# new_esplay.net
KiCad netlist of a schematic drawn in EAGLE
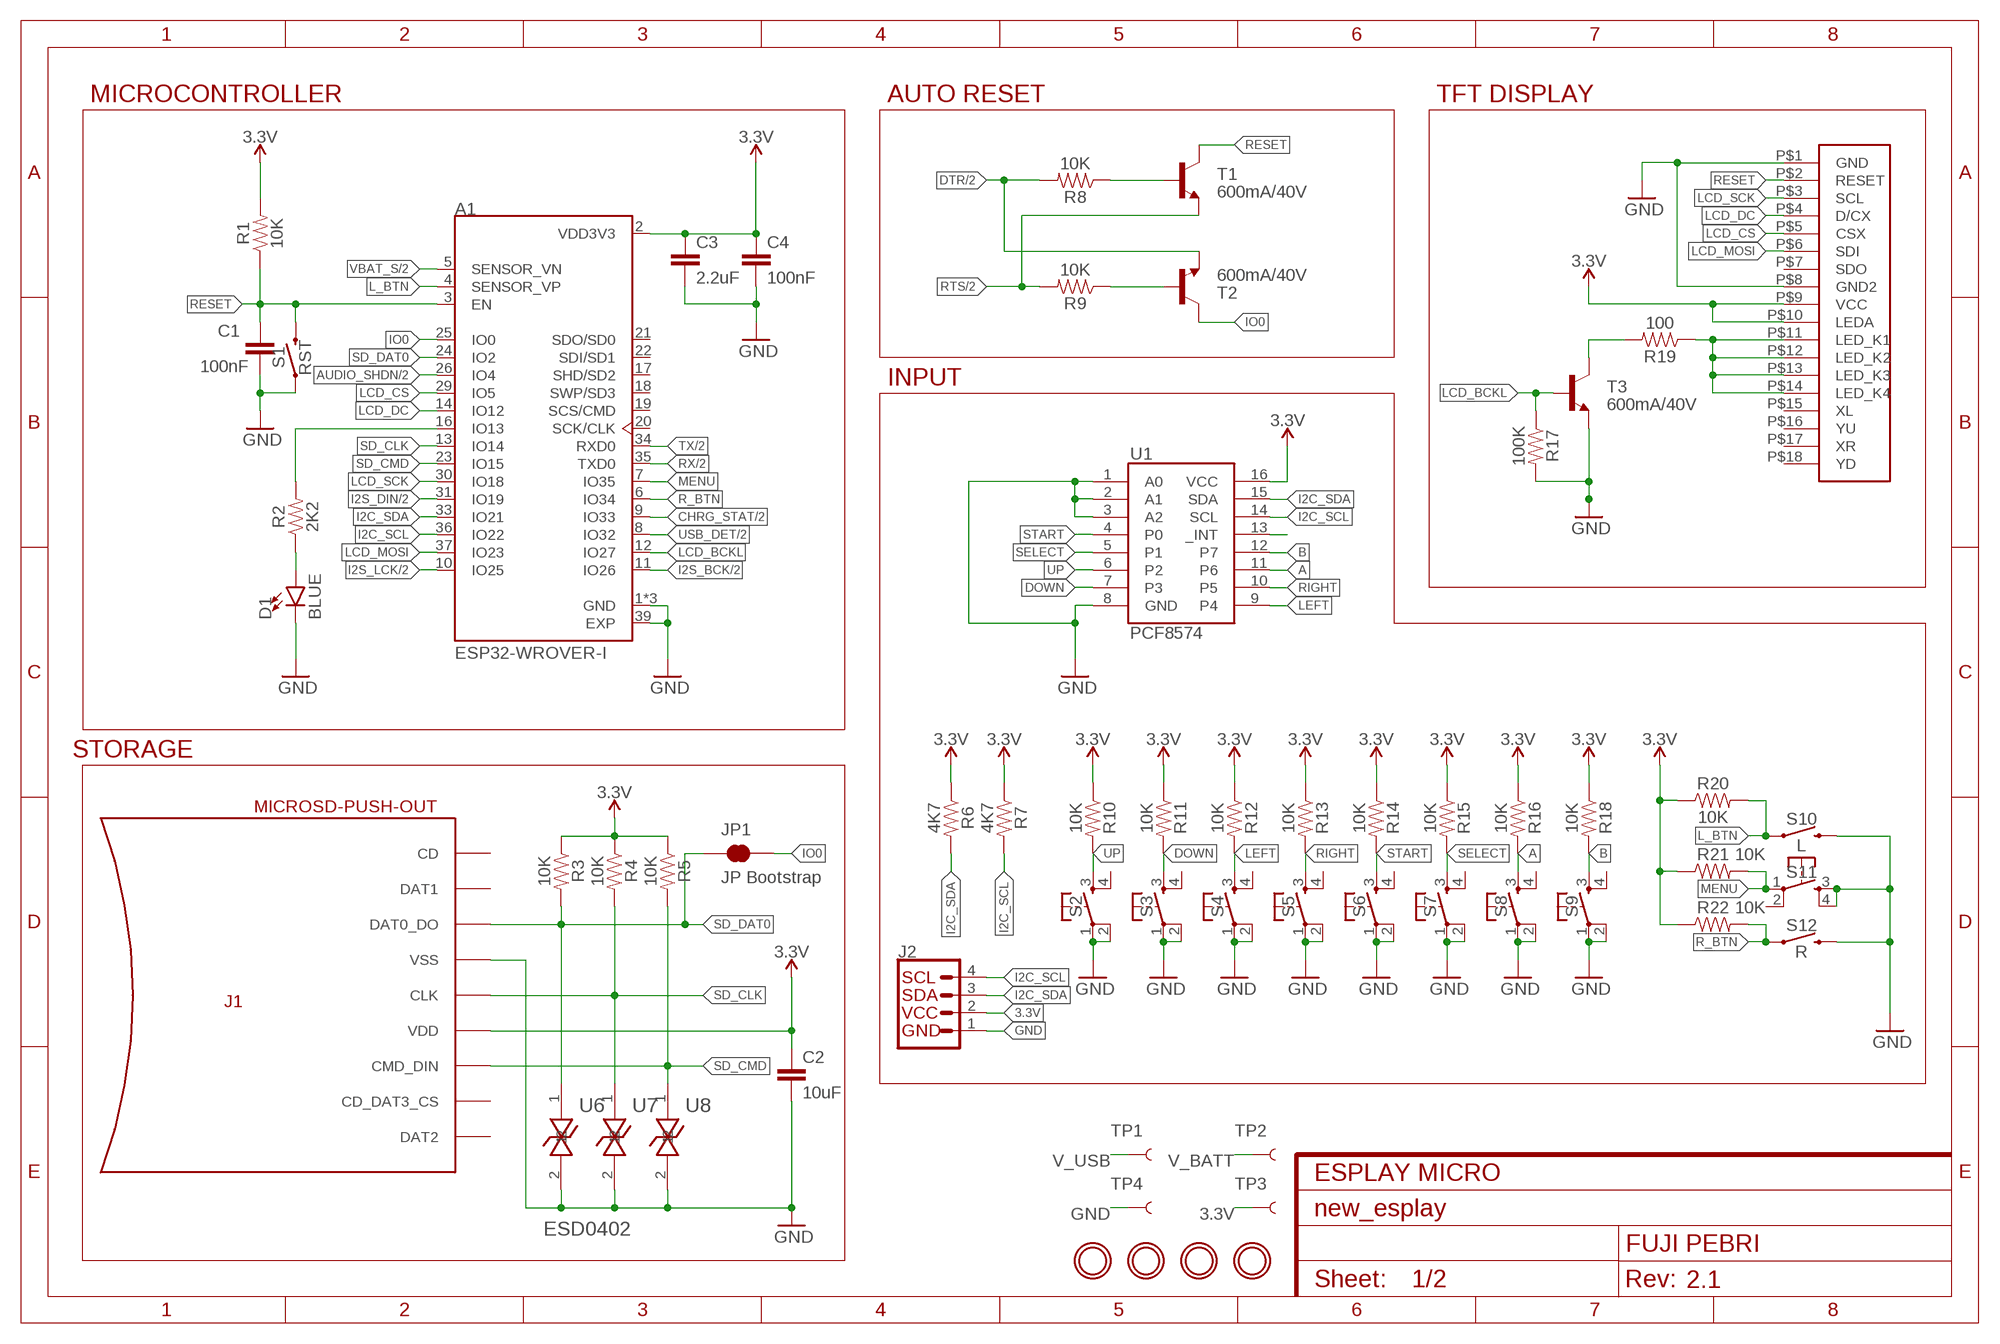
[diagram p0: schematic, sheet 1]
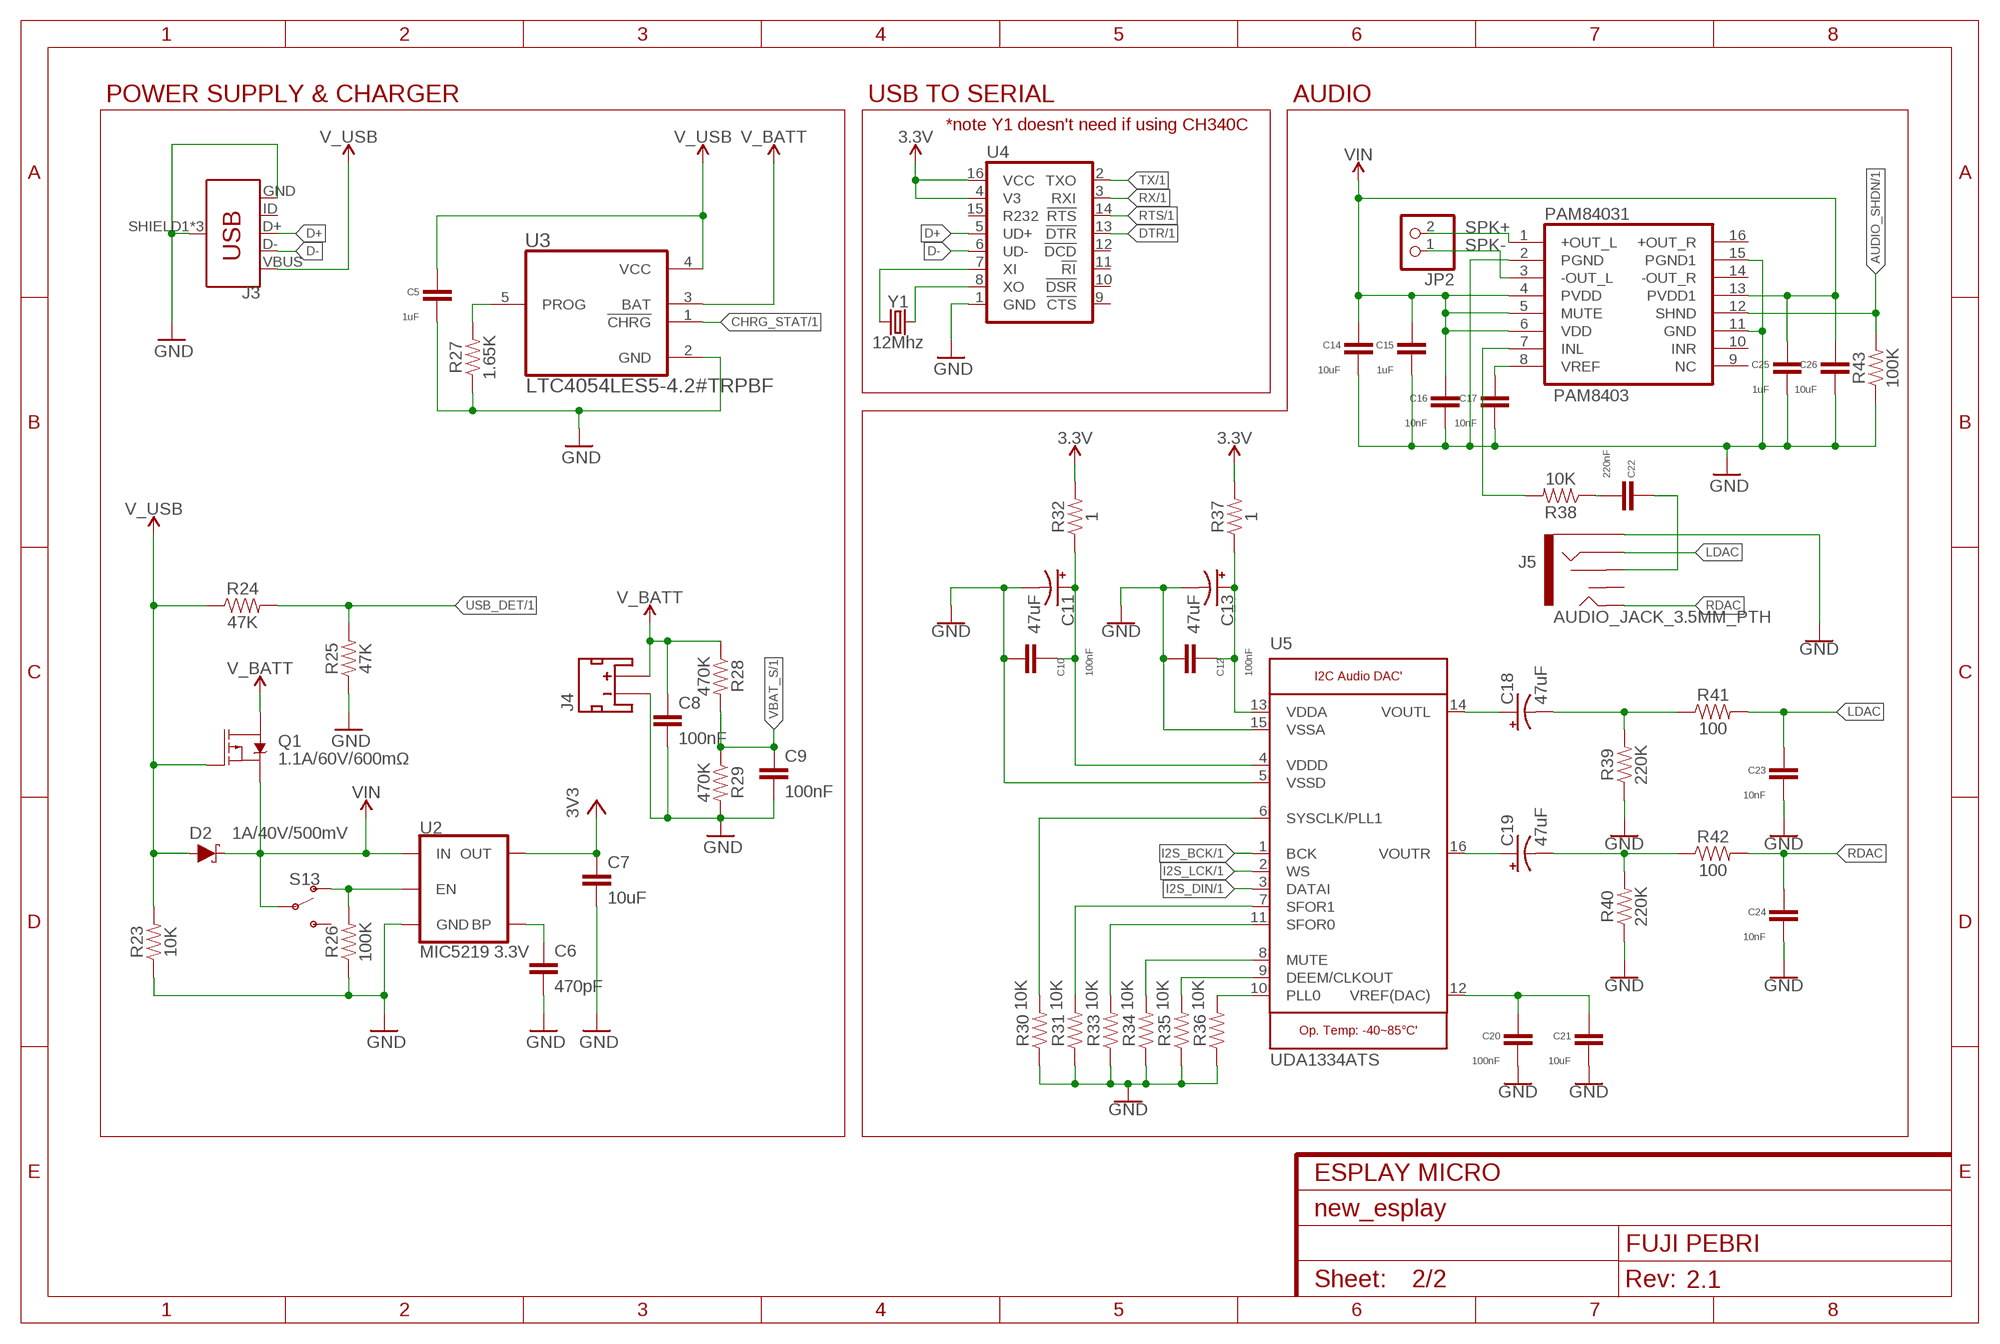
[diagram p1: schematic, sheet 2]

(export (version "E")
  (design (tool "Eeschema 10.0.6"))
  (components
    (comp (ref "A1")
      (value "ESP32-WROVER-I")
      (footprint "eagle-import:XCVR_ESP32-WROVER-I")
      (fields (field (name "MF") "Espressif Systems"))
      (libsource (lib "eagle-import") (part "ESP32-WROVER-I"))
    )
    (comp (ref "C1")
      (value "100nF")
      (footprint "eagle-import:0805")
      (libsource (lib "eagle-import") (part "2.2UF-0805-25V-(+80/-20%)"))
    )
    (comp (ref "C2")
      (value "10uF")
      (footprint "eagle-import:0805")
      (libsource (lib "eagle-import") (part "2.2UF-0805-25V-(+80/-20%)"))
    )
    (comp (ref "C3")
      (value "2.2uF")
      (footprint "eagle-import:0805")
      (libsource (lib "eagle-import") (part "2.2UF-0805-25V-(+80/-20%)"))
    )
    (comp (ref "C4")
      (value "100nF")
      (footprint "eagle-import:0805")
      (libsource (lib "eagle-import") (part "2.2UF-0805-25V-(+80/-20%)"))
    )
    (comp (ref "D1")
      (value "BLUE")
      (footprint "eagle-import:LED-0603")
      (libsource (lib "eagle-import") (part "LED-BLUE0603"))
    )
    (comp (ref "H1")
      (value "MICROBUILDER_MOUNTINGHOLE3.0THIN")
      (footprint "eagle-import:MICROBUILDER_MOUNTINGHOLE_3.0_PLATEDTHIN")
      (libsource (lib "eagle-import") (part "MICROBUILDER_MOUNTINGHOLE3.0THIN"))
    )
    (comp (ref "H2")
      (value "MICROBUILDER_MOUNTINGHOLE3.0THIN")
      (footprint "eagle-import:MICROBUILDER_MOUNTINGHOLE_3.0_PLATEDTHIN")
      (libsource (lib "eagle-import") (part "MICROBUILDER_MOUNTINGHOLE3.0THIN"))
    )
    (comp (ref "H3")
      (value "MICROBUILDER_MOUNTINGHOLE3.0THIN")
      (footprint "eagle-import:MICROBUILDER_MOUNTINGHOLE_3.0_PLATEDTHIN")
      (libsource (lib "eagle-import") (part "MICROBUILDER_MOUNTINGHOLE3.0THIN"))
    )
    (comp (ref "H4")
      (value "MICROBUILDER_MOUNTINGHOLE3.0THIN")
      (footprint "eagle-import:MICROBUILDER_MOUNTINGHOLE_3.0_PLATEDTHIN")
      (libsource (lib "eagle-import") (part "MICROBUILDER_MOUNTINGHOLE3.0THIN"))
    )
    (comp (ref "J1")
      (value "MICROSD-PUSH-OUT")
      (footprint "eagle-import:MICROSD-PUSH-OUT")
      (libsource (lib "eagle-import") (part "MICROSD-PUSH-OUT"))
    )
    (comp (ref "J2")
      (value "QWIIC_CONNECTORJS-1MM")
      (footprint "eagle-import:1X04_1MM_RA")
      (libsource (lib "eagle-import") (part "QWIIC_CONNECTORJS-1MM"))
    )
    (comp (ref "JP1")
      (value "JP Bootstrap")
      (footprint "eagle-import:SMT-JUMPER_2_NC_TRACE_NO-SILK")
      (libsource (lib "eagle-import") (part "JUMPER-SMT_2_NC_TRACE_NO-SILK"))
    )
    (comp (ref "LCD1")
      (value "ILI9341-2.4")
      (footprint "eagle-import:ILI9341-2.4")
      (libsource (lib "eagle-import") (part "ILI9341-2.4"))
    )
    (comp (ref "R1")
      (value "10K")
      (footprint "eagle-import:0805")
      (libsource (lib "eagle-import") (part "0.22OHM-0805-1/4W-1%"))
    )
    (comp (ref "R2")
      (value "2K2")
      (footprint "eagle-import:0805")
      (libsource (lib "eagle-import") (part "0.22OHM-0805-1/4W-1%"))
    )
    (comp (ref "R3")
      (value "10K")
      (footprint "eagle-import:0805")
      (libsource (lib "eagle-import") (part "0.22OHM-0805-1/4W-1%"))
    )
    (comp (ref "R4")
      (value "10K")
      (footprint "eagle-import:0805")
      (libsource (lib "eagle-import") (part "0.22OHM-0805-1/4W-1%"))
    )
    (comp (ref "R5")
      (value "10K")
      (footprint "eagle-import:0805")
      (libsource (lib "eagle-import") (part "0.22OHM-0805-1/4W-1%"))
    )
    (comp (ref "R6")
      (value "4K7")
      (footprint "eagle-import:0805")
      (libsource (lib "eagle-import") (part "0.22OHM-0805-1/4W-1%"))
    )
    (comp (ref "R7")
      (value "4K7")
      (footprint "eagle-import:0805")
      (libsource (lib "eagle-import") (part "0.22OHM-0805-1/4W-1%"))
    )
    (comp (ref "R8")
      (value "10K")
      (footprint "eagle-import:0805")
      (libsource (lib "eagle-import") (part "0.22OHM-0805-1/4W-1%"))
    )
    (comp (ref "R9")
      (value "10K")
      (footprint "eagle-import:0805")
      (libsource (lib "eagle-import") (part "0.22OHM-0805-1/4W-1%"))
    )
    (comp (ref "R10")
      (value "10K")
      (footprint "eagle-import:0805")
      (libsource (lib "eagle-import") (part "0.22OHM-0805-1/4W-1%"))
    )
    (comp (ref "R11")
      (value "10K")
      (footprint "eagle-import:0805")
      (libsource (lib "eagle-import") (part "0.22OHM-0805-1/4W-1%"))
    )
    (comp (ref "R12")
      (value "10K")
      (footprint "eagle-import:0805")
      (libsource (lib "eagle-import") (part "0.22OHM-0805-1/4W-1%"))
    )
    (comp (ref "R13")
      (value "10K")
      (footprint "eagle-import:0805")
      (libsource (lib "eagle-import") (part "0.22OHM-0805-1/4W-1%"))
    )
    (comp (ref "R14")
      (value "10K")
      (footprint "eagle-import:0805")
      (libsource (lib "eagle-import") (part "0.22OHM-0805-1/4W-1%"))
    )
    (comp (ref "R15")
      (value "10K")
      (footprint "eagle-import:0805")
      (libsource (lib "eagle-import") (part "0.22OHM-0805-1/4W-1%"))
    )
    (comp (ref "R16")
      (value "10K")
      (footprint "eagle-import:0805")
      (libsource (lib "eagle-import") (part "0.22OHM-0805-1/4W-1%"))
    )
    (comp (ref "R17")
      (value "100K")
      (footprint "eagle-import:0805")
      (libsource (lib "eagle-import") (part "0.22OHM-0805-1/4W-1%"))
    )
    (comp (ref "R18")
      (value "10K")
      (footprint "eagle-import:0805")
      (libsource (lib "eagle-import") (part "0.22OHM-0805-1/4W-1%"))
    )
    (comp (ref "R19")
      (value "100")
      (footprint "eagle-import:0805")
      (libsource (lib "eagle-import") (part "0.22OHM-0805-1/4W-1%"))
    )
    (comp (ref "R20")
      (value "10K")
      (footprint "eagle-import:0805")
      (libsource (lib "eagle-import") (part "0.22OHM-0805-1/4W-1%"))
    )
    (comp (ref "R21")
      (value "10K")
      (footprint "eagle-import:0805")
      (libsource (lib "eagle-import") (part "0.22OHM-0805-1/4W-1%"))
    )
    (comp (ref "R22")
      (value "10K")
      (footprint "eagle-import:0805")
      (libsource (lib "eagle-import") (part "0.22OHM-0805-1/4W-1%"))
    )
    (comp (ref "S1")
      (value "RST")
      (footprint "eagle-import:TACTILE_SWITCH_SMD_4.6X2.8MM")
      (libsource (lib "eagle-import") (part "MOMENTARY-SWITCH-SPST-SMD-4.6X2.8MM"))
    )
    (comp (ref "S2")
      (value "MOMENTARY-SWITCH-SPST-2-SMD-5.2MM")
      (footprint "eagle-import:TACTILE_SWITCH_SMD_5.2MM")
      (libsource (lib "eagle-import") (part "MOMENTARY-SWITCH-SPST-2-SMD-5.2MM"))
    )
    (comp (ref "S3")
      (value "MOMENTARY-SWITCH-SPST-2-SMD-5.2MM")
      (footprint "eagle-import:TACTILE_SWITCH_SMD_5.2MM")
      (libsource (lib "eagle-import") (part "MOMENTARY-SWITCH-SPST-2-SMD-5.2MM"))
    )
    (comp (ref "S4")
      (value "MOMENTARY-SWITCH-SPST-2-SMD-5.2MM")
      (footprint "eagle-import:TACTILE_SWITCH_SMD_5.2MM")
      (libsource (lib "eagle-import") (part "MOMENTARY-SWITCH-SPST-2-SMD-5.2MM"))
    )
    (comp (ref "S5")
      (value "MOMENTARY-SWITCH-SPST-2-SMD-5.2MM")
      (footprint "eagle-import:TACTILE_SWITCH_SMD_5.2MM")
      (libsource (lib "eagle-import") (part "MOMENTARY-SWITCH-SPST-2-SMD-5.2MM"))
    )
    (comp (ref "S6")
      (value "MOMENTARY-SWITCH-SPST-2-SMD-5.2MM")
      (footprint "eagle-import:TACTILE_SWITCH_SMD_5.2MM")
      (libsource (lib "eagle-import") (part "MOMENTARY-SWITCH-SPST-2-SMD-5.2MM"))
    )
    (comp (ref "S7")
      (value "MOMENTARY-SWITCH-SPST-2-SMD-5.2MM")
      (footprint "eagle-import:TACTILE_SWITCH_SMD_5.2MM")
      (libsource (lib "eagle-import") (part "MOMENTARY-SWITCH-SPST-2-SMD-5.2MM"))
    )
    (comp (ref "S8")
      (value "MOMENTARY-SWITCH-SPST-2-SMD-5.2MM")
      (footprint "eagle-import:TACTILE_SWITCH_SMD_5.2MM")
      (libsource (lib "eagle-import") (part "MOMENTARY-SWITCH-SPST-2-SMD-5.2MM"))
    )
    (comp (ref "S9")
      (value "MOMENTARY-SWITCH-SPST-2-SMD-5.2MM")
      (footprint "eagle-import:TACTILE_SWITCH_SMD_5.2MM")
      (libsource (lib "eagle-import") (part "MOMENTARY-SWITCH-SPST-2-SMD-5.2MM"))
    )
    (comp (ref "S10")
      (value "L")
      (footprint "eagle-import:TACTILE_SWITCH_PTH_RIGHT_ANGLE_KIT")
      (libsource (lib "eagle-import") (part "MOMENTARY-SWITCH-SPST-PTH-RIGHT-ANGLE-KIT"))
    )
    (comp (ref "S11")
      (value "MOMENTARY-SWITCH-SPST-2-SMD-5.2MM")
      (footprint "eagle-import:TACTILE_SWITCH_SMD_5.2MM")
      (libsource (lib "eagle-import") (part "MOMENTARY-SWITCH-SPST-2-SMD-5.2MM"))
    )
    (comp (ref "S12")
      (value "R")
      (footprint "eagle-import:TACTILE_SWITCH_PTH_RIGHT_ANGLE_KIT")
      (libsource (lib "eagle-import") (part "MOMENTARY-SWITCH-SPST-PTH-RIGHT-ANGLE-KIT"))
    )
    (comp (ref "T1")
      (value "600mA/40V")
      (footprint "eagle-import:SOT23-3")
      (libsource (lib "eagle-import") (part "TRANS_NPN-MMBT2222AL"))
    )
    (comp (ref "T2")
      (value "600mA/40V")
      (footprint "eagle-import:SOT23-3")
      (libsource (lib "eagle-import") (part "TRANS_NPN-MMBT2222AL"))
    )
    (comp (ref "T3")
      (value "600mA/40V")
      (footprint "eagle-import:SOT23-3")
      (libsource (lib "eagle-import") (part "TRANS_NPN-MMBT2222AL"))
    )
    (comp (ref "TP1")
      (value "TEST-POINT3")
      (footprint "eagle-import:PAD.03X.03")
      (libsource (lib "eagle-import") (part "TEST-POINT3"))
    )
    (comp (ref "TP2")
      (value "TEST-POINT3")
      (footprint "eagle-import:PAD.03X.03")
      (libsource (lib "eagle-import") (part "TEST-POINT3"))
    )
    (comp (ref "TP3")
      (value "TEST-POINT3")
      (footprint "eagle-import:PAD.03X.03")
      (libsource (lib "eagle-import") (part "TEST-POINT3"))
    )
    (comp (ref "TP4")
      (value "TEST-POINT3")
      (footprint "eagle-import:PAD.03X.03")
      (libsource (lib "eagle-import") (part "TEST-POINT3"))
    )
    (comp (ref "U1")
      (value "PCF8574")
      (footprint "eagle-import:SO16")
      (fields (field (name "MF") "Texas Instruments"))
      (libsource (lib "eagle-import") (part "PCF8574"))
    )
    (comp (ref "U6")
      (value "ESD0402")
      (footprint "eagle-import:ESD0402")
      (libsource (lib "eagle-import") (part "ESD0402"))
    )
    (comp (ref "U7")
      (value "ESD0402")
      (footprint "eagle-import:ESD0402")
      (libsource (lib "eagle-import") (part "ESD0402"))
    )
    (comp (ref "U8")
      (value "ESD0402")
      (footprint "eagle-import:ESD0402")
      (libsource (lib "eagle-import") (part "ESD0402"))
    )
    (comp (ref "C5")
      (value "1uF")
      (footprint "eagle-import:0805")
      (libsource (lib "eagle-import") (part "2.2UF-0805-25V-(+80/-20%)"))
    )
    (comp (ref "C6")
      (value "470pF")
      (footprint "eagle-import:0805")
      (libsource (lib "eagle-import") (part "2.2UF-0805-25V-(+80/-20%)"))
    )
    (comp (ref "C7")
      (value "10uF")
      (footprint "eagle-import:0805")
      (libsource (lib "eagle-import") (part "2.2UF-0805-25V-(+80/-20%)"))
    )
    (comp (ref "C8")
      (value "100nF")
      (footprint "eagle-import:0805")
      (libsource (lib "eagle-import") (part "2.2UF-0805-25V-(+80/-20%)"))
    )
    (comp (ref "C9")
      (value "100nF")
      (footprint "eagle-import:0805")
      (libsource (lib "eagle-import") (part "2.2UF-0805-25V-(+80/-20%)"))
    )
    (comp (ref "C10")
      (value "100nF")
      (footprint "eagle-import:0805")
      (libsource (lib "eagle-import") (part "2.2UF-0805-25V-(+80/-20%)"))
    )
    (comp (ref "C11")
      (value "47uF")
      (footprint "eagle-import:EIA3528")
      (libsource (lib "eagle-import") (part "47UF-POLAR-EIA3528-10V-10%"))
    )
    (comp (ref "C12")
      (value "100nF")
      (footprint "eagle-import:0805")
      (libsource (lib "eagle-import") (part "2.2UF-0805-25V-(+80/-20%)"))
    )
    (comp (ref "C13")
      (value "47uF")
      (footprint "eagle-import:EIA3528")
      (libsource (lib "eagle-import") (part "47UF-POLAR-EIA3528-10V-10%"))
    )
    (comp (ref "C14")
      (value "10uF")
      (footprint "eagle-import:0805")
      (libsource (lib "eagle-import") (part "2.2UF-0805-25V-(+80/-20%)"))
    )
    (comp (ref "C15")
      (value "1uF")
      (footprint "eagle-import:0805")
      (libsource (lib "eagle-import") (part "2.2UF-0805-25V-(+80/-20%)"))
    )
    (comp (ref "C16")
      (value "10nF")
      (footprint "eagle-import:0805")
      (libsource (lib "eagle-import") (part "2.2UF-0805-25V-(+80/-20%)"))
    )
    (comp (ref "C17")
      (value "10nF")
      (footprint "eagle-import:0805")
      (libsource (lib "eagle-import") (part "2.2UF-0805-25V-(+80/-20%)"))
    )
    (comp (ref "C18")
      (value "47uF")
      (footprint "eagle-import:EIA3528")
      (libsource (lib "eagle-import") (part "47UF-POLAR-EIA3528-10V-10%"))
    )
    (comp (ref "C19")
      (value "47uF")
      (footprint "eagle-import:EIA3528")
      (libsource (lib "eagle-import") (part "47UF-POLAR-EIA3528-10V-10%"))
    )
    (comp (ref "C20")
      (value "100nF")
      (footprint "eagle-import:0805")
      (libsource (lib "eagle-import") (part "2.2UF-0805-25V-(+80/-20%)"))
    )
    (comp (ref "C21")
      (value "10uF")
      (footprint "eagle-import:0805")
      (libsource (lib "eagle-import") (part "2.2UF-0805-25V-(+80/-20%)"))
    )
    (comp (ref "C22")
      (value "220nF")
      (footprint "eagle-import:0805")
      (libsource (lib "eagle-import") (part "2.2UF-0805-25V-(+80/-20%)"))
    )
    (comp (ref "C23")
      (value "10nF")
      (footprint "eagle-import:0805")
      (libsource (lib "eagle-import") (part "2.2UF-0805-25V-(+80/-20%)"))
    )
    (comp (ref "C24")
      (value "10nF")
      (footprint "eagle-import:0805")
      (libsource (lib "eagle-import") (part "2.2UF-0805-25V-(+80/-20%)"))
    )
    (comp (ref "C25")
      (value "1uF")
      (footprint "eagle-import:0805")
      (libsource (lib "eagle-import") (part "2.2UF-0805-25V-(+80/-20%)"))
    )
    (comp (ref "C26")
      (value "10uF")
      (footprint "eagle-import:0805")
      (libsource (lib "eagle-import") (part "2.2UF-0805-25V-(+80/-20%)"))
    )
    (comp (ref "D2")
      (value "1A/40V/500mV")
      (footprint "eagle-import:SMA-DIODE")
      (libsource (lib "eagle-import") (part "DIODE-SCHOTTKY-SS14"))
    )
    (comp (ref "J3")
      (value "USB_MICRO-B_FEMALE-SMT")
      (footprint "eagle-import:USB-B-MICRO-SMD")
      (libsource (lib "eagle-import") (part "USB_MICRO-B_FEMALE-SMT"))
    )
    (comp (ref "J4")
      (value "JST_2MM_MALE")
      (footprint "eagle-import:JST-2-SMD")
      (libsource (lib "eagle-import") (part "JST_2MM_MALE"))
    )
    (comp (ref "J5")
      (value "AUDIO_JACK_3.5MM_PTH")
      (footprint "eagle-import:AUDIO-JACK")
      (libsource (lib "eagle-import") (part "AUDIO_JACK_3.5MM_PTH"))
    )
    (comp (ref "JP2")
      (value "PINHD-1X2_2.00")
      (footprint "eagle-import:1X02M")
      (libsource (lib "eagle-import") (part "PINHD-1X2_2.00"))
    )
    (comp (ref "PAM84031")
      (value "PAM8403")
      (footprint "eagle-import:SOP-16")
      (libsource (lib "eagle-import") (part "PAM8403"))
    )
    (comp (ref "Q1")
      (value "1.1A/60V/600mΩ")
      (footprint "eagle-import:SOT23-3")
      (libsource (lib "eagle-import") (part "MOSFET_PCH-SI2309DS"))
    )
    (comp (ref "R23")
      (value "10K")
      (footprint "eagle-import:0805")
      (libsource (lib "eagle-import") (part "0.22OHM-0805-1/4W-1%"))
    )
    (comp (ref "R24")
      (value "47K")
      (footprint "eagle-import:0805")
      (libsource (lib "eagle-import") (part "0.22OHM-0805-1/4W-1%"))
    )
    (comp (ref "R25")
      (value "47K")
      (footprint "eagle-import:0805")
      (libsource (lib "eagle-import") (part "0.22OHM-0805-1/4W-1%"))
    )
    (comp (ref "R26")
      (value "100K")
      (footprint "eagle-import:0805")
      (libsource (lib "eagle-import") (part "0.22OHM-0805-1/4W-1%"))
    )
    (comp (ref "R27")
      (value "1.65K")
      (footprint "eagle-import:0805")
      (libsource (lib "eagle-import") (part "0.3OHM-0805-1/8W-1%"))
    )
    (comp (ref "R28")
      (value "470K")
      (footprint "eagle-import:0805")
      (libsource (lib "eagle-import") (part "0.22OHM-0805-1/4W-1%"))
    )
    (comp (ref "R29")
      (value "470K")
      (footprint "eagle-import:0805")
      (libsource (lib "eagle-import") (part "0.22OHM-0805-1/4W-1%"))
    )
    (comp (ref "R30")
      (value "10K")
      (footprint "eagle-import:0805")
      (libsource (lib "eagle-import") (part "0.3OHM-0805-1/8W-1%"))
    )
    (comp (ref "R31")
      (value "10K")
      (footprint "eagle-import:0805")
      (libsource (lib "eagle-import") (part "0.3OHM-0805-1/8W-1%"))
    )
    (comp (ref "R32")
      (value "1")
      (footprint "eagle-import:0805")
      (libsource (lib "eagle-import") (part "0.3OHM-0805-1/8W-1%"))
    )
    (comp (ref "R33")
      (value "10K")
      (footprint "eagle-import:0805")
      (libsource (lib "eagle-import") (part "0.3OHM-0805-1/8W-1%"))
    )
    (comp (ref "R34")
      (value "10K")
      (footprint "eagle-import:0805")
      (libsource (lib "eagle-import") (part "0.3OHM-0805-1/8W-1%"))
    )
    (comp (ref "R35")
      (value "10K")
      (footprint "eagle-import:0805")
      (libsource (lib "eagle-import") (part "0.3OHM-0805-1/8W-1%"))
    )
    (comp (ref "R36")
      (value "10K")
      (footprint "eagle-import:0805")
      (libsource (lib "eagle-import") (part "0.3OHM-0805-1/8W-1%"))
    )
    (comp (ref "R37")
      (value "1")
      (footprint "eagle-import:0805")
      (libsource (lib "eagle-import") (part "0.3OHM-0805-1/8W-1%"))
    )
    (comp (ref "R38")
      (value "10K")
      (footprint "eagle-import:0805")
      (libsource (lib "eagle-import") (part "0.3OHM-0805-1/8W-1%"))
    )
    (comp (ref "R39")
      (value "220K")
      (footprint "eagle-import:0805")
      (libsource (lib "eagle-import") (part "0.3OHM-0805-1/8W-1%"))
    )
    (comp (ref "R40")
      (value "220K")
      (footprint "eagle-import:0805")
      (libsource (lib "eagle-import") (part "0.3OHM-0805-1/8W-1%"))
    )
    (comp (ref "R41")
      (value "100")
      (footprint "eagle-import:0805")
      (libsource (lib "eagle-import") (part "0.3OHM-0805-1/8W-1%"))
    )
    (comp (ref "R42")
      (value "100")
      (footprint "eagle-import:0805")
      (libsource (lib "eagle-import") (part "0.3OHM-0805-1/8W-1%"))
    )
    (comp (ref "R43")
      (value "100K")
      (footprint "eagle-import:0805")
      (libsource (lib "eagle-import") (part "0.3OHM-0805-1/8W-1%"))
    )
    (comp (ref "S13")
      (value "SWITCH-SPDT-SMD-RIGHT-ANGLE")
      (footprint "eagle-import:SWITCH_SPST_SMD_A")
      (libsource (lib "eagle-import") (part "SWITCH-SPDT-SMD-RIGHT-ANGLE"))
    )
    (comp (ref "U2")
      (value "MIC5219 3.3V")
      (footprint "eagle-import:SOT23-5")
      (libsource (lib "eagle-import") (part "V_REG_MIC52193.3V"))
    )
    (comp (ref "U3")
      (value "LTC4054LES5-4.2#TRPBF")
      (footprint "eagle-import:SOT95P280X100-5N")
      (fields
        (field (name "DIGI-KEY_PART_NUMBER") "LTC4054LES5-4.2#TRPBFCT-ND")
        (field (name "MF") "Linear Technology/Analog")
      )
      (libsource (lib "eagle-import") (part "LTC4054LES5-4.2#TRPBF"))
    )
    (comp (ref "U4")
      (value "CH340G")
      (footprint "eagle-import:SO016")
      (libsource (lib "eagle-import") (part "CH340GSMD"))
    )
    (comp (ref "U5")
      (value "UDA1334ATS")
      (footprint "eagle-import:MICROBUILDER_SSOP16_4.4MM")
      (libsource (lib "eagle-import") (part "MICROBUILDER_AUDIO_I2S_UDA1334{dblquote}{dblquote}"))
    )
    (comp (ref "Y1")
      (value "12Mhz")
      (footprint "eagle-import:CRYSTAL-SMD-5X3.2-4PAD")
      (libsource (lib "eagle-import") (part "CRYSTALSMD-5X3.2-4PAD"))
    )
  )
  (nets
    (net (code "1") (name "3.3V") (class "Default")
      (node (ref "A1") (pin "2") (pinfunction "VDD3V3_2") (pintype "power_in"))
      (node (ref "C2") (pin "1") (pinfunction "1_1") (pintype "passive"))
      (node (ref "C3") (pin "1") (pinfunction "1_1") (pintype "passive"))
      (node (ref "C4") (pin "1") (pinfunction "1_1") (pintype "passive"))
      (node (ref "C7") (pin "1") (pinfunction "1_1") (pintype "passive"))
      (node (ref "J1") (pin "4") (pinfunction "VDD_4") (pintype "bidirectional"))
      (node (ref "J2") (pin "2") (pinfunction "2_2") (pintype "power_in"))
      (node (ref "LCD1") (pin "P$10") (pinfunction "LEDA_P$10") (pintype "bidirectional"))
      (node (ref "LCD1") (pin "P$9") (pinfunction "VCC_P$9") (pintype "bidirectional"))
      (node (ref "R1") (pin "2") (pinfunction "2_2") (pintype "passive"))
      (node (ref "R10") (pin "1") (pinfunction "1_1") (pintype "passive"))
      (node (ref "R11") (pin "1") (pinfunction "1_1") (pintype "passive"))
      (node (ref "R12") (pin "1") (pinfunction "1_1") (pintype "passive"))
      (node (ref "R13") (pin "1") (pinfunction "1_1") (pintype "passive"))
      (node (ref "R14") (pin "1") (pinfunction "1_1") (pintype "passive"))
      (node (ref "R15") (pin "1") (pinfunction "1_1") (pintype "passive"))
      (node (ref "R16") (pin "1") (pinfunction "1_1") (pintype "passive"))
      (node (ref "R18") (pin "1") (pinfunction "1_1") (pintype "passive"))
      (node (ref "R20") (pin "1") (pinfunction "1_1") (pintype "passive"))
      (node (ref "R21") (pin "1") (pinfunction "1_1") (pintype "passive"))
      (node (ref "R22") (pin "1") (pinfunction "1_1") (pintype "passive"))
      (node (ref "R3") (pin "1") (pinfunction "1_1") (pintype "passive"))
      (node (ref "R32") (pin "2") (pinfunction "2_2") (pintype "passive"))
      (node (ref "R37") (pin "2") (pinfunction "2_2") (pintype "passive"))
      (node (ref "R4") (pin "1") (pinfunction "1_1") (pintype "passive"))
      (node (ref "R5") (pin "1") (pinfunction "1_1") (pintype "passive"))
      (node (ref "R6") (pin "1") (pinfunction "1_1") (pintype "passive"))
      (node (ref "R7") (pin "1") (pinfunction "1_1") (pintype "passive"))
      (node (ref "TP3") (pin "P$1") (pinfunction "1_P$1") (pintype "bidirectional"))
      (node (ref "U1") (pin "16") (pinfunction "VCC_16") (pintype "bidirectional"))
      (node (ref "U2") (pin "5") (pinfunction "OUT_5") (pintype "passive"))
      (node (ref "U4") (pin "16") (pinfunction "VCC_16") (pintype "bidirectional"))
      (node (ref "U4") (pin "4") (pinfunction "V3_4") (pintype "bidirectional"))
    )
    (net (code "2") (name "A") (class "Default")
      (node (ref "R16") (pin "2") (pinfunction "2_2") (pintype "passive"))
      (node (ref "S8") (pin "3") (pinfunction "3_3") (pintype "passive"))
      (node (ref "U1") (pin "11") (pinfunction "P6_11") (pintype "bidirectional"))
    )
    (net (code "3") (name "AUDIO_SHDN") (class "Default")
      (node (ref "A1") (pin "26") (pinfunction "IO4_26") (pintype "bidirectional"))
      (node (ref "PAM84031") (pin "12") (pinfunction "SHND_12") (pintype "output"))
      (node (ref "R43") (pin "2") (pinfunction "2_2") (pintype "passive"))
    )
    (net (code "4") (name "B") (class "Default")
      (node (ref "R18") (pin "2") (pinfunction "2_2") (pintype "passive"))
      (node (ref "S9") (pin "3") (pinfunction "3_3") (pintype "passive"))
      (node (ref "U1") (pin "12") (pinfunction "P7_12") (pintype "bidirectional"))
    )
    (net (code "5") (name "CHRG_STAT") (class "Default")
      (node (ref "A1") (pin "9") (pinfunction "IO33_9") (pintype "bidirectional"))
      (node (ref "U3") (pin "1") (pinfunction "~{CHRG}_1") (pintype "output"))
    )
    (net (code "6") (name "D+") (class "Default")
      (node (ref "J3") (pin "D+") (pinfunction "D+_D+") (pintype "bidirectional"))
      (node (ref "U4") (pin "5") (pinfunction "UD+_5") (pintype "bidirectional"))
    )
    (net (code "7") (name "D-") (class "Default")
      (node (ref "J3") (pin "D-") (pinfunction "D-_D-") (pintype "bidirectional"))
      (node (ref "U4") (pin "6") (pinfunction "UD-_6") (pintype "bidirectional"))
    )
    (net (code "8") (name "DOWN") (class "Default")
      (node (ref "R11") (pin "2") (pinfunction "2_2") (pintype "passive"))
      (node (ref "S3") (pin "3") (pinfunction "3_3") (pintype "passive"))
      (node (ref "U1") (pin "7") (pinfunction "P3_7") (pintype "bidirectional"))
    )
    (net (code "9") (name "DTR") (class "Default")
      (node (ref "R8") (pin "2") (pinfunction "2_2") (pintype "passive"))
      (node (ref "T2") (pin "2") (pinfunction "E_2") (pintype "passive"))
      (node (ref "U4") (pin "13") (pinfunction "~{DTR}_13") (pintype "bidirectional"))
    )
    (net (code "10") (name "GND") (class "Default")
      (node (ref "A1") (pin "1") (pinfunction "GND_1") (pintype "power_in"))
      (node (ref "A1") (pin "15") (pinfunction "GND_15") (pintype "power_in"))
      (node (ref "A1") (pin "38") (pinfunction "GND_38") (pintype "power_in"))
      (node (ref "A1") (pin "39") (pinfunction "EXP_39") (pintype "power_in"))
      (node (ref "C1") (pin "2") (pinfunction "2_2") (pintype "passive"))
      (node (ref "C10") (pin "1") (pinfunction "1_1") (pintype "passive"))
      (node (ref "C11") (pin "C") (pinfunction "-_C") (pintype "passive"))
      (node (ref "C12") (pin "1") (pinfunction "1_1") (pintype "passive"))
      (node (ref "C13") (pin "C") (pinfunction "-_C") (pintype "passive"))
      (node (ref "C14") (pin "1") (pinfunction "1_1") (pintype "passive"))
      (node (ref "C15") (pin "1") (pinfunction "1_1") (pintype "passive"))
      (node (ref "C16") (pin "1") (pinfunction "1_1") (pintype "passive"))
      (node (ref "C17") (pin "1") (pinfunction "1_1") (pintype "passive"))
      (node (ref "C2") (pin "2") (pinfunction "2_2") (pintype "passive"))
      (node (ref "C20") (pin "1") (pinfunction "1_1") (pintype "passive"))
      (node (ref "C21") (pin "1") (pinfunction "1_1") (pintype "passive"))
      (node (ref "C23") (pin "1") (pinfunction "1_1") (pintype "passive"))
      (node (ref "C24") (pin "1") (pinfunction "1_1") (pintype "passive"))
      (node (ref "C25") (pin "1") (pinfunction "1_1") (pintype "passive"))
      (node (ref "C26") (pin "1") (pinfunction "1_1") (pintype "passive"))
      (node (ref "C3") (pin "2") (pinfunction "2_2") (pintype "passive"))
      (node (ref "C4") (pin "2") (pinfunction "2_2") (pintype "passive"))
      (node (ref "C5") (pin "1") (pinfunction "1_1") (pintype "passive"))
      (node (ref "C6") (pin "2") (pinfunction "2_2") (pintype "passive"))
      (node (ref "C7") (pin "2") (pinfunction "2_2") (pintype "passive"))
      (node (ref "C8") (pin "2") (pinfunction "2_2") (pintype "passive"))
      (node (ref "C9") (pin "2") (pinfunction "2_2") (pintype "passive"))
      (node (ref "D1") (pin "C") (pinfunction "C_C") (pintype "passive"))
      (node (ref "J1") (pin "6") (pinfunction "VSS_6") (pintype "bidirectional"))
      (node (ref "J1") (pin "G1") (pinfunction "VSS_G1") (pintype "bidirectional"))
      (node (ref "J1") (pin "G2") (pinfunction "VSS_G2") (pintype "bidirectional"))
      (node (ref "J1") (pin "G3") (pinfunction "VSS_G3") (pintype "bidirectional"))
      (node (ref "J1") (pin "G4") (pinfunction "VSS_G4") (pintype "bidirectional"))
      (node (ref "J2") (pin "1") (pinfunction "1_1") (pintype "power_in"))
      (node (ref "J3") (pin "GND") (pinfunction "GND_GND") (pintype "power_in"))
      (node (ref "J3") (pin "SHIELD1") (pinfunction "SHIELD_SHIELD1") (pintype "bidirectional"))
      (node (ref "J3") (pin "SHIELD2") (pinfunction "SHIELD_SHIELD2") (pintype "bidirectional"))
      (node (ref "J3") (pin "SHIELD3") (pinfunction "SHIELD_SHIELD3") (pintype "bidirectional"))
      (node (ref "J4") (pin "1") (pinfunction "-_1") (pintype "bidirectional"))
      (node (ref "J5") (pin "SLEEVE") (pinfunction "SLEEVE_SLEEVE") (pintype "bidirectional"))
      (node (ref "LCD1") (pin "P$1") (pinfunction "GND_P$1") (pintype "bidirectional"))
      (node (ref "LCD1") (pin "P$8") (pinfunction "GND2_P$8") (pintype "bidirectional"))
      (node (ref "PAM84031") (pin "11") (pinfunction "GND_11") (pintype "output"))
      (node (ref "PAM84031") (pin "15") (pinfunction "PGND1_15") (pintype "output"))
      (node (ref "PAM84031") (pin "2") (pinfunction "PGND_2") (pintype "input"))
      (node (ref "R17") (pin "2") (pinfunction "2_2") (pintype "passive"))
      (node (ref "R23") (pin "1") (pinfunction "1_1") (pintype "passive"))
      (node (ref "R25") (pin "1") (pinfunction "1_1") (pintype "passive"))
      (node (ref "R26") (pin "1") (pinfunction "1_1") (pintype "passive"))
      (node (ref "R27") (pin "1") (pinfunction "1_1") (pintype "passive"))
      (node (ref "R29") (pin "2") (pinfunction "2_2") (pintype "passive"))
      (node (ref "R30") (pin "1") (pinfunction "1_1") (pintype "passive"))
      (node (ref "R31") (pin "1") (pinfunction "1_1") (pintype "passive"))
      (node (ref "R33") (pin "1") (pinfunction "1_1") (pintype "passive"))
      (node (ref "R34") (pin "1") (pinfunction "1_1") (pintype "passive"))
      (node (ref "R35") (pin "1") (pinfunction "1_1") (pintype "passive"))
      (node (ref "R36") (pin "1") (pinfunction "1_1") (pintype "passive"))
      (node (ref "R39") (pin "1") (pinfunction "1_1") (pintype "passive"))
      (node (ref "R40") (pin "1") (pinfunction "1_1") (pintype "passive"))
      (node (ref "R43") (pin "1") (pinfunction "1_1") (pintype "passive"))
      (node (ref "S1") (pin "1") (pinfunction "1_1") (pintype "passive"))
      (node (ref "S1") (pin "2") (pinfunction "1_2") (pintype "passive"))
      (node (ref "S10") (pin "2") (pinfunction "2_2") (pintype "passive"))
      (node (ref "S11") (pin "3") (pinfunction "3_3") (pintype "passive"))
      (node (ref "S11") (pin "4") (pinfunction "4_4") (pintype "passive"))
      (node (ref "S12") (pin "2") (pinfunction "2_2") (pintype "passive"))
      (node (ref "S2") (pin "1") (pinfunction "1_1") (pintype "passive"))
      (node (ref "S2") (pin "2") (pinfunction "2_2") (pintype "passive"))
      (node (ref "S3") (pin "1") (pinfunction "1_1") (pintype "passive"))
      (node (ref "S3") (pin "2") (pinfunction "2_2") (pintype "passive"))
      (node (ref "S4") (pin "1") (pinfunction "1_1") (pintype "passive"))
      (node (ref "S4") (pin "2") (pinfunction "2_2") (pintype "passive"))
      (node (ref "S5") (pin "1") (pinfunction "1_1") (pintype "passive"))
      (node (ref "S5") (pin "2") (pinfunction "2_2") (pintype "passive"))
      (node (ref "S6") (pin "1") (pinfunction "1_1") (pintype "passive"))
      (node (ref "S6") (pin "2") (pinfunction "2_2") (pintype "passive"))
      (node (ref "S7") (pin "1") (pinfunction "1_1") (pintype "passive"))
      (node (ref "S7") (pin "2") (pinfunction "2_2") (pintype "passive"))
      (node (ref "S8") (pin "1") (pinfunction "1_1") (pintype "passive"))
      (node (ref "S8") (pin "2") (pinfunction "2_2") (pintype "passive"))
      (node (ref "S9") (pin "1") (pinfunction "1_1") (pintype "passive"))
      (node (ref "S9") (pin "2") (pinfunction "2_2") (pintype "passive"))
      (node (ref "T3") (pin "2") (pinfunction "E_2") (pintype "passive"))
      (node (ref "TP4") (pin "P$1") (pinfunction "1_P$1") (pintype "bidirectional"))
      (node (ref "U1") (pin "1") (pinfunction "A0_1") (pintype "bidirectional"))
      (node (ref "U1") (pin "2") (pinfunction "A1_2") (pintype "bidirectional"))
      (node (ref "U1") (pin "3") (pinfunction "A2_3") (pintype "bidirectional"))
      (node (ref "U1") (pin "8") (pinfunction "GND_8") (pintype "bidirectional"))
      (node (ref "U2") (pin "2") (pinfunction "GND_2") (pintype "input"))
      (node (ref "U3") (pin "2") (pinfunction "GND_2") (pintype "power_in"))
      (node (ref "U4") (pin "1") (pinfunction "GND_1") (pintype "bidirectional"))
      (node (ref "U5") (pin "15") (pinfunction "VSSA_15") (pintype "power_in"))
      (node (ref "U5") (pin "5") (pinfunction "VSSD_5") (pintype "power_in"))
      (node (ref "U6") (pin "2") (pinfunction "2_2") (pintype "bidirectional"))
      (node (ref "U7") (pin "2") (pinfunction "2_2") (pintype "bidirectional"))
      (node (ref "U8") (pin "2") (pinfunction "2_2") (pintype "bidirectional"))
    )
    (net (code "11") (name "I2C_SCL") (class "Default")
      (node (ref "A1") (pin "36") (pinfunction "IO22_36") (pintype "bidirectional"))
      (node (ref "J2") (pin "4") (pinfunction "4_4") (pintype "passive"))
      (node (ref "R7") (pin "2") (pinfunction "2_2") (pintype "passive"))
      (node (ref "U1") (pin "14") (pinfunction "SCL_14") (pintype "bidirectional"))
    )
    (net (code "12") (name "I2C_SDA") (class "Default")
      (node (ref "A1") (pin "33") (pinfunction "IO21_33") (pintype "bidirectional"))
      (node (ref "J2") (pin "3") (pinfunction "3_3") (pintype "passive"))
      (node (ref "R6") (pin "2") (pinfunction "2_2") (pintype "passive"))
      (node (ref "U1") (pin "15") (pinfunction "SDA_15") (pintype "bidirectional"))
    )
    (net (code "13") (name "I2S_BCK") (class "Default")
      (node (ref "A1") (pin "11") (pinfunction "IO26_11") (pintype "bidirectional"))
      (node (ref "U5") (pin "1") (pinfunction "BCK_1") (pintype "input"))
    )
    (net (code "14") (name "I2S_DIN") (class "Default")
      (node (ref "A1") (pin "31") (pinfunction "IO19_31") (pintype "bidirectional"))
      (node (ref "U5") (pin "3") (pinfunction "DATAI_3") (pintype "input"))
    )
    (net (code "15") (name "I2S_LCK") (class "Default")
      (node (ref "A1") (pin "10") (pinfunction "IO25_10") (pintype "bidirectional"))
      (node (ref "U5") (pin "2") (pinfunction "WS_2") (pintype "input"))
    )
    (net (code "16") (name "IO0") (class "Default")
      (node (ref "A1") (pin "25") (pinfunction "IO0_25") (pintype "bidirectional"))
      (node (ref "JP1") (pin "2") (pinfunction "2_2") (pintype "passive"))
      (node (ref "T2") (pin "3") (pinfunction "C_3") (pintype "passive"))
    )
    (net (code "17") (name "LCD_BCKL") (class "Default")
      (node (ref "A1") (pin "12") (pinfunction "IO27_12") (pintype "bidirectional"))
      (node (ref "R17") (pin "1") (pinfunction "1_1") (pintype "passive"))
      (node (ref "T3") (pin "1") (pinfunction "B_1") (pintype "passive"))
    )
    (net (code "18") (name "LCD_CS") (class "Default")
      (node (ref "A1") (pin "29") (pinfunction "IO5_29") (pintype "bidirectional"))
      (node (ref "LCD1") (pin "P$5") (pinfunction "CSX_P$5") (pintype "bidirectional"))
    )
    (net (code "19") (name "LCD_DC") (class "Default")
      (node (ref "A1") (pin "14") (pinfunction "IO12_14") (pintype "bidirectional"))
      (node (ref "LCD1") (pin "P$4") (pinfunction "D/CX_P$4") (pintype "bidirectional"))
    )
    (net (code "20") (name "LCD_MOSI") (class "Default")
      (node (ref "A1") (pin "37") (pinfunction "IO23_37") (pintype "bidirectional"))
      (node (ref "LCD1") (pin "P$6") (pinfunction "SDI_P$6") (pintype "bidirectional"))
    )
    (net (code "21") (name "LCD_SCK") (class "Default")
      (node (ref "A1") (pin "30") (pinfunction "IO18_30") (pintype "bidirectional"))
      (node (ref "LCD1") (pin "P$3") (pinfunction "SCL_P$3") (pintype "bidirectional"))
    )
    (net (code "22") (name "LDAC") (class "Default")
      (node (ref "C23") (pin "2") (pinfunction "2_2") (pintype "passive"))
      (node (ref "J5") (pin "RING") (pinfunction "RING_RING") (pintype "bidirectional"))
      (node (ref "R41") (pin "2") (pinfunction "2_2") (pintype "passive"))
    )
    (net (code "23") (name "LEFT") (class "Default")
      (node (ref "R12") (pin "2") (pinfunction "2_2") (pintype "passive"))
      (node (ref "S4") (pin "3") (pinfunction "3_3") (pintype "passive"))
      (node (ref "U1") (pin "9") (pinfunction "P4_9") (pintype "bidirectional"))
    )
    (net (code "24") (name "L_BTN") (class "Default")
      (node (ref "A1") (pin "4") (pinfunction "SENSOR_VP_4") (pintype "input"))
      (node (ref "R20") (pin "2") (pinfunction "2_2") (pintype "passive"))
      (node (ref "S10") (pin "1") (pinfunction "1_1") (pintype "passive"))
    )
    (net (code "25") (name "MENU") (class "Default")
      (node (ref "A1") (pin "7") (pinfunction "IO35_7") (pintype "input"))
      (node (ref "R21") (pin "2") (pinfunction "2_2") (pintype "passive"))
      (node (ref "S11") (pin "1") (pinfunction "1_1") (pintype "passive"))
    )
    (net (code "26") (name "Net-(A1-IO13)") (class "Default")
      (node (ref "A1") (pin "16") (pinfunction "IO13_16") (pintype "bidirectional"))
      (node (ref "R2") (pin "2") (pinfunction "2_2") (pintype "passive"))
    )
    (net (code "27") (name "Net-(C11-+)") (class "Default")
      (node (ref "C10") (pin "2") (pinfunction "2_2") (pintype "passive"))
      (node (ref "C11") (pin "A") (pinfunction "+_A") (pintype "passive"))
      (node (ref "R32") (pin "1") (pinfunction "1_1") (pintype "passive"))
      (node (ref "U5") (pin "4") (pinfunction "VDDD_4") (pintype "power_in"))
    )
    (net (code "28") (name "Net-(C13-+)") (class "Default")
      (node (ref "C12") (pin "2") (pinfunction "2_2") (pintype "passive"))
      (node (ref "C13") (pin "A") (pinfunction "+_A") (pintype "passive"))
      (node (ref "R37") (pin "1") (pinfunction "1_1") (pintype "passive"))
      (node (ref "U5") (pin "13") (pinfunction "VDDA_13") (pintype "power_in"))
    )
    (net (code "29") (name "Net-(C18-+)") (class "Default")
      (node (ref "C18") (pin "A") (pinfunction "+_A") (pintype "passive"))
      (node (ref "U5") (pin "14") (pinfunction "VOUTL_14") (pintype "output"))
    )
    (net (code "30") (name "Net-(C18--)") (class "Default")
      (node (ref "C18") (pin "C") (pinfunction "-_C") (pintype "passive"))
      (node (ref "R39") (pin "2") (pinfunction "2_2") (pintype "passive"))
      (node (ref "R41") (pin "1") (pinfunction "1_1") (pintype "passive"))
    )
    (net (code "31") (name "Net-(C19-+)") (class "Default")
      (node (ref "C19") (pin "A") (pinfunction "+_A") (pintype "passive"))
      (node (ref "U5") (pin "16") (pinfunction "VOUTR_16") (pintype "output"))
    )
    (net (code "32") (name "Net-(C19--)") (class "Default")
      (node (ref "C19") (pin "C") (pinfunction "-_C") (pintype "passive"))
      (node (ref "R40") (pin "2") (pinfunction "2_2") (pintype "passive"))
      (node (ref "R42") (pin "1") (pinfunction "1_1") (pintype "passive"))
    )
    (net (code "33") (name "Net-(C22-Pad1)") (class "Default")
      (node (ref "C22") (pin "1") (pinfunction "1_1") (pintype "passive"))
      (node (ref "R38") (pin "1") (pinfunction "1_1") (pintype "passive"))
    )
    (net (code "34") (name "Net-(C22-Pad2)") (class "Default")
      (node (ref "C22") (pin "2") (pinfunction "2_2") (pintype "passive"))
      (node (ref "J5") (pin "RSH") (pinfunction "RSH_RSH") (pintype "bidirectional"))
    )
    (net (code "35") (name "Net-(D1-PadA)") (class "Default")
      (node (ref "D1") (pin "A") (pinfunction "A_A") (pintype "passive"))
      (node (ref "R2") (pin "1") (pinfunction "1_1") (pintype "passive"))
    )
    (net (code "36") (name "Net-(LCD1-LED_K1)") (class "Default")
      (node (ref "LCD1") (pin "P$11") (pinfunction "LED_K1_P$11") (pintype "bidirectional"))
      (node (ref "LCD1") (pin "P$12") (pinfunction "LED_K2_P$12") (pintype "bidirectional"))
      (node (ref "LCD1") (pin "P$13") (pinfunction "LED_K3_P$13") (pintype "bidirectional"))
      (node (ref "LCD1") (pin "P$14") (pinfunction "LED_K4_P$14") (pintype "bidirectional"))
      (node (ref "R19") (pin "1") (pinfunction "1_1") (pintype "passive"))
    )
    (net (code "37") (name "Net-(PAM84031-INL)") (class "Default")
      (node (ref "PAM84031") (pin "7") (pinfunction "INL_7") (pintype "input"))
      (node (ref "R38") (pin "2") (pinfunction "2_2") (pintype "passive"))
    )
    (net (code "38") (name "Net-(PAM84031-VREF)") (class "Default")
      (node (ref "C17") (pin "2") (pinfunction "2_2") (pintype "passive"))
      (node (ref "PAM84031") (pin "8") (pinfunction "VREF_8") (pintype "input"))
    )
    (net (code "39") (name "Net-(S13-O)") (class "Default")
      (node (ref "R26") (pin "2") (pinfunction "2_2") (pintype "passive"))
      (node (ref "S13") (pin "1") (pinfunction "O_1") (pintype "passive"))
      (node (ref "U2") (pin "3") (pinfunction "EN_3") (pintype "input"))
    )
    (net (code "40") (name "Net-(T1-B)") (class "Default")
      (node (ref "R8") (pin "1") (pinfunction "1_1") (pintype "passive"))
      (node (ref "T1") (pin "1") (pinfunction "B_1") (pintype "passive"))
    )
    (net (code "41") (name "Net-(T2-B)") (class "Default")
      (node (ref "R9") (pin "1") (pinfunction "1_1") (pintype "passive"))
      (node (ref "T2") (pin "1") (pinfunction "B_1") (pintype "passive"))
    )
    (net (code "42") (name "Net-(T3-C)") (class "Default")
      (node (ref "R19") (pin "2") (pinfunction "2_2") (pintype "passive"))
      (node (ref "T3") (pin "3") (pinfunction "C_3") (pintype "passive"))
    )
    (net (code "43") (name "Net-(U2-BP)") (class "Default")
      (node (ref "C6") (pin "1") (pinfunction "1_1") (pintype "passive"))
      (node (ref "U2") (pin "4") (pinfunction "BP_4") (pintype "input"))
    )
    (net (code "44") (name "Net-(U3-PROG)") (class "Default")
      (node (ref "R27") (pin "2") (pinfunction "2_2") (pintype "passive"))
      (node (ref "U3") (pin "5") (pinfunction "PROG_5") (pintype "input"))
    )
    (net (code "45") (name "Net-(U4-XI)") (class "Default")
      (node (ref "U4") (pin "7") (pinfunction "XI_7") (pintype "bidirectional"))
      (node (ref "Y1") (pin "3") (pinfunction "2_3") (pintype "passive"))
    )
    (net (code "46") (name "Net-(U4-XO)") (class "Default")
      (node (ref "U4") (pin "8") (pinfunction "XO_8") (pintype "bidirectional"))
      (node (ref "Y1") (pin "1") (pinfunction "1_1") (pintype "passive"))
    )
    (net (code "47") (name "Net-(U5-DEEM{slash}CLKOUT)") (class "Default")
      (node (ref "R35") (pin "2") (pinfunction "2_2") (pintype "passive"))
      (node (ref "U5") (pin "9") (pinfunction "DEEM/CLKOUT_9") (pintype "bidirectional"))
    )
    (net (code "48") (name "Net-(U5-MUTE)") (class "Default")
      (node (ref "R34") (pin "2") (pinfunction "2_2") (pintype "passive"))
      (node (ref "U5") (pin "8") (pinfunction "MUTE_8") (pintype "input"))
    )
    (net (code "49") (name "Net-(U5-PLL0)") (class "Default")
      (node (ref "R36") (pin "2") (pinfunction "2_2") (pintype "passive"))
      (node (ref "U5") (pin "10") (pinfunction "PLL0_10") (pintype "input"))
    )
    (net (code "50") (name "Net-(U5-SFOR0)") (class "Default")
      (node (ref "R33") (pin "2") (pinfunction "2_2") (pintype "passive"))
      (node (ref "U5") (pin "11") (pinfunction "SFOR0_11") (pintype "input"))
    )
    (net (code "51") (name "Net-(U5-SFOR1)") (class "Default")
      (node (ref "R31") (pin "2") (pinfunction "2_2") (pintype "passive"))
      (node (ref "U5") (pin "7") (pinfunction "SFOR1_7") (pintype "input"))
    )
    (net (code "52") (name "Net-(U5-SYSCLK{slash}PLL1)") (class "Default")
      (node (ref "R30") (pin "2") (pinfunction "2_2") (pintype "passive"))
      (node (ref "U5") (pin "6") (pinfunction "SYSCLK/PLL1_6") (pintype "input"))
    )
    (net (code "53") (name "Net-(U5-VREF(DAC))") (class "Default")
      (node (ref "C20") (pin "2") (pinfunction "2_2") (pintype "passive"))
      (node (ref "C21") (pin "2") (pinfunction "2_2") (pintype "passive"))
      (node (ref "U5") (pin "12") (pinfunction "VREF(DAC)_12") (pintype "output"))
    )
    (net (code "54") (name "RDAC") (class "Default")
      (node (ref "C24") (pin "2") (pinfunction "2_2") (pintype "passive"))
      (node (ref "J5") (pin "TIP") (pinfunction "TIP_TIP") (pintype "bidirectional"))
      (node (ref "R42") (pin "2") (pinfunction "2_2") (pintype "passive"))
    )
    (net (code "55") (name "RESET") (class "Default")
      (node (ref "A1") (pin "3") (pinfunction "EN_3") (pintype "input"))
      (node (ref "C1") (pin "1") (pinfunction "1_1") (pintype "passive"))
      (node (ref "LCD1") (pin "P$2") (pinfunction "RESET_P$2") (pintype "bidirectional"))
      (node (ref "R1") (pin "1") (pinfunction "1_1") (pintype "passive"))
      (node (ref "S1") (pin "3") (pinfunction "2_3") (pintype "passive"))
      (node (ref "S1") (pin "4") (pinfunction "2_4") (pintype "passive"))
      (node (ref "T1") (pin "3") (pinfunction "C_3") (pintype "passive"))
    )
    (net (code "56") (name "RIGHT") (class "Default")
      (node (ref "R13") (pin "2") (pinfunction "2_2") (pintype "passive"))
      (node (ref "S5") (pin "3") (pinfunction "3_3") (pintype "passive"))
      (node (ref "U1") (pin "10") (pinfunction "P5_10") (pintype "bidirectional"))
    )
    (net (code "57") (name "RTS") (class "Default")
      (node (ref "R9") (pin "2") (pinfunction "2_2") (pintype "passive"))
      (node (ref "T1") (pin "2") (pinfunction "E_2") (pintype "passive"))
      (node (ref "U4") (pin "14") (pinfunction "~{RTS}_14") (pintype "bidirectional"))
    )
    (net (code "58") (name "RX") (class "Default")
      (node (ref "A1") (pin "35") (pinfunction "TXD0_35") (pintype "bidirectional"))
      (node (ref "U4") (pin "3") (pinfunction "RXI_3") (pintype "bidirectional"))
    )
    (net (code "59") (name "R_BTN") (class "Default")
      (node (ref "A1") (pin "6") (pinfunction "IO34_6") (pintype "input"))
      (node (ref "R22") (pin "2") (pinfunction "2_2") (pintype "passive"))
      (node (ref "S12") (pin "1") (pinfunction "1_1") (pintype "passive"))
    )
    (net (code "60") (name "SD_CLK") (class "Default")
      (node (ref "A1") (pin "13") (pinfunction "IO14_13") (pintype "bidirectional"))
      (node (ref "J1") (pin "5") (pinfunction "CLK_5") (pintype "bidirectional"))
      (node (ref "R4") (pin "2") (pinfunction "2_2") (pintype "passive"))
      (node (ref "U7") (pin "1") (pinfunction "1_1") (pintype "bidirectional"))
    )
    (net (code "61") (name "SD_CMD") (class "Default")
      (node (ref "A1") (pin "23") (pinfunction "IO15_23") (pintype "bidirectional"))
      (node (ref "J1") (pin "3") (pinfunction "CMD_DIN_3") (pintype "bidirectional"))
      (node (ref "R5") (pin "2") (pinfunction "2_2") (pintype "passive"))
      (node (ref "U8") (pin "1") (pinfunction "1_1") (pintype "bidirectional"))
    )
    (net (code "62") (name "SD_DAT0") (class "Default")
      (node (ref "A1") (pin "24") (pinfunction "IO2_24") (pintype "bidirectional"))
      (node (ref "J1") (pin "7") (pinfunction "DAT0_DO_7") (pintype "bidirectional"))
      (node (ref "JP1") (pin "1") (pinfunction "1_1") (pintype "passive"))
      (node (ref "R3") (pin "2") (pinfunction "2_2") (pintype "passive"))
      (node (ref "U6") (pin "1") (pinfunction "1_1") (pintype "bidirectional"))
    )
    (net (code "63") (name "SELECT") (class "Default")
      (node (ref "R15") (pin "2") (pinfunction "2_2") (pintype "passive"))
      (node (ref "S7") (pin "3") (pinfunction "3_3") (pintype "passive"))
      (node (ref "U1") (pin "5") (pinfunction "P1_5") (pintype "bidirectional"))
    )
    (net (code "64") (name "SPK+") (class "Default")
      (node (ref "JP2") (pin "2") (pinfunction "2_2") (pintype "passive"))
      (node (ref "PAM84031") (pin "1") (pinfunction "+OUT_L_1") (pintype "input"))
    )
    (net (code "65") (name "SPK-") (class "Default")
      (node (ref "JP2") (pin "1") (pinfunction "1_1") (pintype "passive"))
      (node (ref "PAM84031") (pin "3") (pinfunction "-OUT_L_3") (pintype "input"))
    )
    (net (code "66") (name "START") (class "Default")
      (node (ref "R14") (pin "2") (pinfunction "2_2") (pintype "passive"))
      (node (ref "S6") (pin "3") (pinfunction "3_3") (pintype "passive"))
      (node (ref "U1") (pin "4") (pinfunction "P0_4") (pintype "bidirectional"))
    )
    (net (code "67") (name "TX") (class "Default")
      (node (ref "A1") (pin "34") (pinfunction "RXD0_34") (pintype "bidirectional"))
      (node (ref "U4") (pin "2") (pinfunction "TXO_2") (pintype "bidirectional"))
    )
    (net (code "68") (name "UP") (class "Default")
      (node (ref "R10") (pin "2") (pinfunction "2_2") (pintype "passive"))
      (node (ref "S2") (pin "3") (pinfunction "3_3") (pintype "passive"))
      (node (ref "U1") (pin "6") (pinfunction "P2_6") (pintype "bidirectional"))
    )
    (net (code "69") (name "USB_DET") (class "Default")
      (node (ref "A1") (pin "8") (pinfunction "IO32_8") (pintype "bidirectional"))
      (node (ref "R24") (pin "2") (pinfunction "2_2") (pintype "passive"))
      (node (ref "R25") (pin "2") (pinfunction "2_2") (pintype "passive"))
    )
    (net (code "70") (name "VBAT_S") (class "Default")
      (node (ref "A1") (pin "5") (pinfunction "SENSOR_VN_5") (pintype "input"))
      (node (ref "C9") (pin "1") (pinfunction "1_1") (pintype "passive"))
      (node (ref "R28") (pin "2") (pinfunction "2_2") (pintype "passive"))
      (node (ref "R29") (pin "1") (pinfunction "1_1") (pintype "passive"))
    )
    (net (code "71") (name "VIN") (class "Default")
      (node (ref "C14") (pin "2") (pinfunction "2_2") (pintype "passive"))
      (node (ref "C15") (pin "2") (pinfunction "2_2") (pintype "passive"))
      (node (ref "C16") (pin "2") (pinfunction "2_2") (pintype "passive"))
      (node (ref "C25") (pin "2") (pinfunction "2_2") (pintype "passive"))
      (node (ref "C26") (pin "2") (pinfunction "2_2") (pintype "passive"))
      (node (ref "D2") (pin "C") (pinfunction "C_C") (pintype "passive"))
      (node (ref "PAM84031") (pin "13") (pinfunction "PVDD1_13") (pintype "output"))
      (node (ref "PAM84031") (pin "4") (pinfunction "PVDD_4") (pintype "input"))
      (node (ref "PAM84031") (pin "5") (pinfunction "MUTE_5") (pintype "input"))
      (node (ref "PAM84031") (pin "6") (pinfunction "VDD_6") (pintype "input"))
      (node (ref "Q1") (pin "2") (pinfunction "S_2") (pintype "bidirectional"))
      (node (ref "S13") (pin "2") (pinfunction "P_2") (pintype "passive"))
      (node (ref "U2") (pin "1") (pinfunction "IN_1") (pintype "input"))
    )
    (net (code "72") (name "V_BATT") (class "Default")
      (node (ref "C8") (pin "1") (pinfunction "1_1") (pintype "passive"))
      (node (ref "J4") (pin "2") (pinfunction "+_2") (pintype "bidirectional"))
      (node (ref "Q1") (pin "3") (pinfunction "D_3") (pintype "bidirectional"))
      (node (ref "R28") (pin "1") (pinfunction "1_1") (pintype "passive"))
      (node (ref "TP2") (pin "P$1") (pinfunction "1_P$1") (pintype "bidirectional"))
      (node (ref "U3") (pin "3") (pinfunction "BAT_3") (pintype "output"))
    )
    (net (code "73") (name "V_USB") (class "Default")
      (node (ref "C5") (pin "2") (pinfunction "2_2") (pintype "passive"))
      (node (ref "D2") (pin "A") (pinfunction "A_A") (pintype "passive"))
      (node (ref "J3") (pin "VBUS") (pinfunction "VBUS_VBUS") (pintype "power_in"))
      (node (ref "Q1") (pin "1") (pinfunction "G_1") (pintype "bidirectional"))
      (node (ref "R23") (pin "2") (pinfunction "2_2") (pintype "passive"))
      (node (ref "R24") (pin "1") (pinfunction "1_1") (pintype "passive"))
      (node (ref "TP1") (pin "P$1") (pinfunction "1_P$1") (pintype "bidirectional"))
      (node (ref "U3") (pin "4") (pinfunction "VCC_4") (pintype "power_in"))
    )
    (net (code "74") (name "unconnected-(A1-SCK{slash}CLK-Pad20)") (class "Default")
      (node (ref "A1") (pin "20") (pinfunction "SCK/CLK_20") (pintype "bidirectional"))
    )
    (net (code "75") (name "unconnected-(A1-SCS{slash}CMD-Pad19)") (class "Default")
      (node (ref "A1") (pin "19") (pinfunction "SCS/CMD_19") (pintype "bidirectional"))
    )
    (net (code "76") (name "unconnected-(A1-SDI{slash}SD1-Pad22)") (class "Default")
      (node (ref "A1") (pin "22") (pinfunction "SDI/SD1_22") (pintype "bidirectional"))
    )
    (net (code "77") (name "unconnected-(A1-SDO{slash}SD0-Pad21)") (class "Default")
      (node (ref "A1") (pin "21") (pinfunction "SDO/SD0_21") (pintype "bidirectional"))
    )
    (net (code "78") (name "unconnected-(A1-SHD{slash}SD2-Pad17)") (class "Default")
      (node (ref "A1") (pin "17") (pinfunction "SHD/SD2_17") (pintype "bidirectional"))
    )
    (net (code "79") (name "unconnected-(A1-SWP{slash}SD3-Pad18)") (class "Default")
      (node (ref "A1") (pin "18") (pinfunction "SWP/SD3_18") (pintype "bidirectional"))
    )
    (net (code "80") (name "unconnected-(J1-CD_DAT3_CS-Pad2)") (class "Default")
      (node (ref "J1") (pin "2") (pinfunction "CD_DAT3_CS_2") (pintype "bidirectional"))
    )
    (net (code "81") (name "unconnected-(J1-DAT1-Pad8)") (class "Default")
      (node (ref "J1") (pin "8") (pinfunction "DAT1_8") (pintype "bidirectional"))
    )
    (net (code "82") (name "unconnected-(J1-DAT2-Pad1)") (class "Default")
      (node (ref "J1") (pin "1") (pinfunction "DAT2_1") (pintype "bidirectional"))
    )
    (net (code "83") (name "unconnected-(J1-PadCD)") (class "Default")
      (node (ref "J1") (pin "CD") (pinfunction "CD_CD") (pintype "bidirectional"))
    )
    (net (code "84") (name "unconnected-(J3-PadID)") (class "Default")
      (node (ref "J3") (pin "ID") (pinfunction "ID_ID") (pintype "bidirectional"))
    )
    (net (code "85") (name "unconnected-(J4-PAD1-PadNC1)") (class "Default")
      (node (ref "J4") (pin "NC1") (pinfunction "PAD1_NC1") (pintype "bidirectional"))
    )
    (net (code "86") (name "unconnected-(J4-PAD2-PadNC2)") (class "Default")
      (node (ref "J4") (pin "NC2") (pinfunction "PAD2_NC2") (pintype "bidirectional"))
    )
    (net (code "87") (name "unconnected-(J5-PadTSH)") (class "Default")
      (node (ref "J5") (pin "TSH") (pinfunction "TSH_TSH") (pintype "bidirectional"))
    )
    (net (code "88") (name "unconnected-(LCD1-SDO-PadP$7)") (class "Default")
      (node (ref "LCD1") (pin "P$7") (pinfunction "SDO_P$7") (pintype "bidirectional"))
    )
    (net (code "89") (name "unconnected-(LCD1-XL-PadP$15)") (class "Default")
      (node (ref "LCD1") (pin "P$15") (pinfunction "XL_P$15") (pintype "bidirectional"))
    )
    (net (code "90") (name "unconnected-(LCD1-XR-PadP$17)") (class "Default")
      (node (ref "LCD1") (pin "P$17") (pinfunction "XR_P$17") (pintype "bidirectional"))
    )
    (net (code "91") (name "unconnected-(LCD1-YD-PadP$18)") (class "Default")
      (node (ref "LCD1") (pin "P$18") (pinfunction "YD_P$18") (pintype "bidirectional"))
    )
    (net (code "92") (name "unconnected-(LCD1-YU-PadP$16)") (class "Default")
      (node (ref "LCD1") (pin "P$16") (pinfunction "YU_P$16") (pintype "bidirectional"))
    )
    (net (code "93") (name "unconnected-(PAM84031-+OUT_R-Pad16)") (class "Default")
      (node (ref "PAM84031") (pin "16") (pinfunction "+OUT_R_16") (pintype "output"))
    )
    (net (code "94") (name "unconnected-(PAM84031--OUT_R-Pad14)") (class "Default")
      (node (ref "PAM84031") (pin "14") (pinfunction "-OUT_R_14") (pintype "output"))
    )
    (net (code "95") (name "unconnected-(PAM84031-INR-Pad10)") (class "Default")
      (node (ref "PAM84031") (pin "10") (pinfunction "INR_10") (pintype "output"))
    )
    (net (code "96") (name "unconnected-(PAM84031-NC-Pad9)") (class "Default")
      (node (ref "PAM84031") (pin "9") (pinfunction "NC_9") (pintype "output"))
    )
    (net (code "97") (name "unconnected-(S2-Pad4)") (class "Default")
      (node (ref "S2") (pin "4") (pinfunction "4_4") (pintype "passive"))
    )
    (net (code "98") (name "unconnected-(S3-Pad4)") (class "Default")
      (node (ref "S3") (pin "4") (pinfunction "4_4") (pintype "passive"))
    )
    (net (code "99") (name "unconnected-(S4-Pad4)") (class "Default")
      (node (ref "S4") (pin "4") (pinfunction "4_4") (pintype "passive"))
    )
    (net (code "100") (name "unconnected-(S5-Pad4)") (class "Default")
      (node (ref "S5") (pin "4") (pinfunction "4_4") (pintype "passive"))
    )
    (net (code "101") (name "unconnected-(S6-Pad4)") (class "Default")
      (node (ref "S6") (pin "4") (pinfunction "4_4") (pintype "passive"))
    )
    (net (code "102") (name "unconnected-(S7-Pad4)") (class "Default")
      (node (ref "S7") (pin "4") (pinfunction "4_4") (pintype "passive"))
    )
    (net (code "103") (name "unconnected-(S8-Pad4)") (class "Default")
      (node (ref "S8") (pin "4") (pinfunction "4_4") (pintype "passive"))
    )
    (net (code "104") (name "unconnected-(S9-Pad4)") (class "Default")
      (node (ref "S9") (pin "4") (pinfunction "4_4") (pintype "passive"))
    )
    (net (code "105") (name "unconnected-(S11-Pad2)") (class "Default")
      (node (ref "S11") (pin "2") (pinfunction "2_2") (pintype "passive"))
    )
    (net (code "106") (name "unconnected-(S13-S-Pad3)") (class "Default")
      (node (ref "S13") (pin "3") (pinfunction "S_3") (pintype "passive"))
    )
    (net (code "107") (name "unconnected-(U1-_INT-Pad13)") (class "Default")
      (node (ref "U1") (pin "13") (pinfunction "_INT_13") (pintype "bidirectional"))
    )
    (net (code "108") (name "unconnected-(U4-R232-Pad15)") (class "Default")
      (node (ref "U4") (pin "15") (pinfunction "R232_15") (pintype "bidirectional"))
    )
    (net (code "109") (name "unconnected-(U4-~{CTS}-Pad9)") (class "Default")
      (node (ref "U4") (pin "9") (pinfunction "~{CTS}_9") (pintype "bidirectional"))
    )
    (net (code "110") (name "unconnected-(U4-~{DCD}-Pad12)") (class "Default")
      (node (ref "U4") (pin "12") (pinfunction "~{DCD}_12") (pintype "bidirectional"))
    )
    (net (code "111") (name "unconnected-(U4-~{DSR}-Pad10)") (class "Default")
      (node (ref "U4") (pin "10") (pinfunction "~{DSR}_10") (pintype "bidirectional"))
    )
    (net (code "112") (name "unconnected-(U4-~{RI}-Pad11)") (class "Default")
      (node (ref "U4") (pin "11") (pinfunction "~{RI}_11") (pintype "bidirectional"))
    )
  )
)
